# Drive.net
KiCad netlist of a schematic drawn in Altium Designer
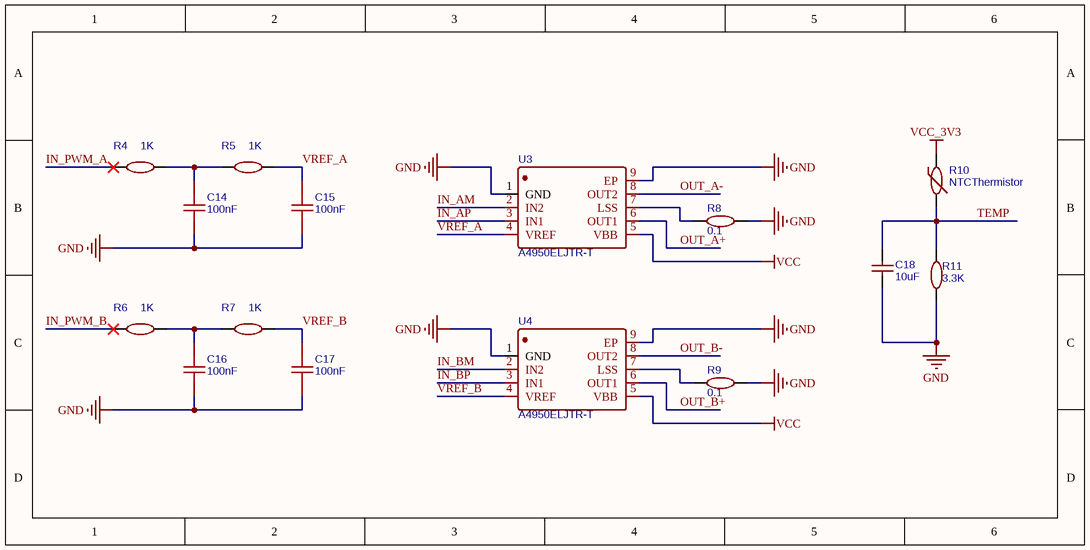
[diagram p0: Drive.SchDoc]

(export (version "E")
  (design (tool "Eeschema 10.0.6"))
  (components
    (comp (ref "C14")
      (value "100nF")
      (footprint "C0603")
      (fields
        (field (name "BOM_MANUFACTURER PART") "CL10B104KB8NNNC")
        (field (name "BOM_SUPPLIER PART") "C1591")
      )
      (libsource (lib "0.1uF") (part "100nF"))
    )
    (comp (ref "C15")
      (value "100nF")
      (footprint "C0603")
      (fields
        (field (name "BOM_MANUFACTURER PART") "CL10B104KB8NNNC")
        (field (name "BOM_SUPPLIER PART") "C1591")
      )
      (libsource (lib "0.1uF") (part "100nF"))
    )
    (comp (ref "C16")
      (value "100nF")
      (footprint "C0603")
      (fields
        (field (name "BOM_MANUFACTURER PART") "CL10B104KB8NNNC")
        (field (name "BOM_SUPPLIER PART") "C1591")
      )
      (libsource (lib "0.1uF") (part "100nF"))
    )
    (comp (ref "C17")
      (value "100nF")
      (footprint "C0603")
      (fields
        (field (name "BOM_MANUFACTURER PART") "CL10B104KB8NNNC")
        (field (name "BOM_SUPPLIER PART") "C1591")
      )
      (libsource (lib "0.1uF") (part "100nF"))
    )
    (comp (ref "C18")
      (value "10uF")
      (footprint "C1206")
      (fields
        (field (name "BOM_MANUFACTURER PART") "CL31A106KBHNNNE")
        (field (name "BOM_SUPPLIER PART") "C13585")
      )
      (libsource (lib "10uF") (part "10uF"))
    )
    (comp (ref "R4")
      (value "1K")
      (footprint "R0603")
      (fields
        (field (name "BOM_MANUFACTURER PART") "0603WAF1001T5E")
        (field (name "BOM_SUPPLIER PART") "C21190")
      )
      (libsource (lib "1K") (part "1K"))
    )
    (comp (ref "R5")
      (value "1K")
      (footprint "R0603")
      (fields
        (field (name "BOM_MANUFACTURER PART") "0603WAF1001T5E")
        (field (name "BOM_SUPPLIER PART") "C21190")
      )
      (libsource (lib "1K") (part "1K"))
    )
    (comp (ref "R6")
      (value "1K")
      (footprint "R0603")
      (fields
        (field (name "BOM_MANUFACTURER PART") "0603WAF1001T5E")
        (field (name "BOM_SUPPLIER PART") "C21190")
      )
      (libsource (lib "1K") (part "1K"))
    )
    (comp (ref "R7")
      (value "1K")
      (footprint "R0603")
      (fields
        (field (name "BOM_MANUFACTURER PART") "0603WAF1001T5E")
        (field (name "BOM_SUPPLIER PART") "C21190")
      )
      (libsource (lib "1K") (part "1K"))
    )
    (comp (ref "R8")
      (value "0.1")
      (footprint "R1206")
      (fields
        (field (name "BOM_MANUFACTURER PART") "1206W4F100LT5E")
        (field (name "BOM_SUPPLIER PART") "C25334")
      )
      (libsource (lib "0.1R") (part "0.1"))
    )
    (comp (ref "R9")
      (value "0.1")
      (footprint "R1206")
      (fields
        (field (name "BOM_MANUFACTURER PART") "1206W4F100LT5E")
        (field (name "BOM_SUPPLIER PART") "C25334")
      )
      (libsource (lib "0.1R") (part "0.1"))
    )
    (comp (ref "R10")
      (value "NTCThermistor")
      (footprint "R0402")
      (fields
        (field (name "BOM_MANUFACTURER PART") "NCP15XH103F03RC")
        (field (name "BOM_SUPPLIER PART") "C77131")
      )
      (libsource (lib "10K THERMISTOR") (part "NTCThermistor"))
    )
    (comp (ref "R11")
      (value "3.3K")
      (footprint "R0603_NEW")
      (fields
        (field (name "BOM_MANUFACTURER PART") "0603WAF3301T5E")
        (field (name "BOM_SUPPLIER PART") "C22978")
      )
      (libsource (lib "3.3K") (part "3.3K"))
    )
    (comp (ref "U3")
      (value "A4950ELJTR-T")
      (footprint "SOIC-8_L4.9-W3.9-P1.27-LS6.0-BL-EP")
      (fields (field (name "BOM_SUPPLIER PART") "C82404"))
      (libsource (lib "A4950") (part "A4950ELJTR-T"))
    )
    (comp (ref "U4")
      (value "A4950ELJTR-T")
      (footprint "SOIC-8_L4.9-W3.9-P1.27-LS6.0-BL-EP")
      (fields (field (name "BOM_SUPPLIER PART") "C82404"))
      (libsource (lib "A4950") (part "A4950ELJTR-T"))
    )
  )
  (nets
    (net (code "1") (name "/IN_AM") (class "Default")
      (node (ref "U3") (pin "2") (pinfunction "IN2_2") (pintype "passive"))
    )
    (net (code "2") (name "/IN_AP") (class "Default")
      (node (ref "U3") (pin "3") (pinfunction "IN1_3") (pintype "passive"))
    )
    (net (code "3") (name "/IN_BM") (class "Default")
      (node (ref "U4") (pin "2") (pinfunction "IN2_2") (pintype "passive"))
    )
    (net (code "4") (name "/IN_BP") (class "Default")
      (node (ref "U4") (pin "3") (pinfunction "IN1_3") (pintype "passive"))
    )
    (net (code "5") (name "/IN_PWM_A") (class "Default")
      (node (ref "R4") (pin "1") (pinfunction "1_1") (pintype "passive+no_connect"))
    )
    (net (code "6") (name "/IN_PWM_B") (class "Default")
      (node (ref "R6") (pin "1") (pinfunction "1_1") (pintype "passive+no_connect"))
    )
    (net (code "7") (name "/OUT_A+") (class "Default")
      (node (ref "U3") (pin "6") (pinfunction "OUT1_6") (pintype "passive"))
    )
    (net (code "8") (name "/OUT_A-") (class "Default")
      (node (ref "U3") (pin "8") (pinfunction "OUT2_8") (pintype "passive"))
    )
    (net (code "9") (name "/OUT_B+") (class "Default")
      (node (ref "U4") (pin "6") (pinfunction "OUT1_6") (pintype "passive"))
    )
    (net (code "10") (name "/OUT_B-") (class "Default")
      (node (ref "U4") (pin "8") (pinfunction "OUT2_8") (pintype "passive"))
    )
    (net (code "11") (name "/TEMP") (class "Default")
      (node (ref "C18") (pin "2") (pinfunction "2_2") (pintype "passive"))
      (node (ref "R10") (pin "2") (pinfunction "2_2") (pintype "passive"))
      (node (ref "R11") (pin "2") (pinfunction "2_2") (pintype "passive"))
    )
    (net (code "12") (name "/VREF_A") (class "Default")
      (node (ref "C15") (pin "2") (pinfunction "2_2") (pintype "passive"))
      (node (ref "R5") (pin "2") (pinfunction "2_2") (pintype "passive"))
      (node (ref "U3") (pin "4") (pinfunction "VREF_4") (pintype "passive"))
    )
    (net (code "13") (name "/VREF_B") (class "Default")
      (node (ref "C17") (pin "2") (pinfunction "2_2") (pintype "passive"))
      (node (ref "R7") (pin "2") (pinfunction "2_2") (pintype "passive"))
      (node (ref "U4") (pin "4") (pinfunction "VREF_4") (pintype "passive"))
    )
    (net (code "14") (name "GND") (class "Default")
      (node (ref "C14") (pin "1") (pinfunction "1_1") (pintype "passive"))
      (node (ref "C15") (pin "1") (pinfunction "1_1") (pintype "passive"))
      (node (ref "C16") (pin "1") (pinfunction "1_1") (pintype "passive"))
      (node (ref "C17") (pin "1") (pinfunction "1_1") (pintype "passive"))
      (node (ref "C18") (pin "1") (pinfunction "1_1") (pintype "passive"))
      (node (ref "R11") (pin "1") (pinfunction "1_1") (pintype "passive"))
      (node (ref "R8") (pin "2") (pinfunction "2_2") (pintype "passive"))
      (node (ref "R9") (pin "2") (pinfunction "2_2") (pintype "passive"))
      (node (ref "U3") (pin "1") (pinfunction "GND_1") (pintype "passive"))
      (node (ref "U3") (pin "9") (pinfunction "EP_9") (pintype "passive"))
      (node (ref "U4") (pin "1") (pinfunction "GND_1") (pintype "passive"))
      (node (ref "U4") (pin "9") (pinfunction "EP_9") (pintype "passive"))
    )
    (net (code "15") (name "Net-(C14-Pad2)") (class "Default")
      (node (ref "C14") (pin "2") (pinfunction "2_2") (pintype "passive"))
      (node (ref "R4") (pin "2") (pinfunction "2_2") (pintype "passive"))
      (node (ref "R5") (pin "1") (pinfunction "1_1") (pintype "passive"))
    )
    (net (code "16") (name "Net-(C16-Pad2)") (class "Default")
      (node (ref "C16") (pin "2") (pinfunction "2_2") (pintype "passive"))
      (node (ref "R6") (pin "2") (pinfunction "2_2") (pintype "passive"))
      (node (ref "R7") (pin "1") (pinfunction "1_1") (pintype "passive"))
    )
    (net (code "17") (name "Net-(U3-LSS)") (class "Default")
      (node (ref "R8") (pin "1") (pinfunction "1_1") (pintype "passive"))
      (node (ref "U3") (pin "7") (pinfunction "LSS_7") (pintype "passive"))
    )
    (net (code "18") (name "Net-(U4-LSS)") (class "Default")
      (node (ref "R9") (pin "1") (pinfunction "1_1") (pintype "passive"))
      (node (ref "U4") (pin "7") (pinfunction "LSS_7") (pintype "passive"))
    )
    (net (code "19") (name "VCC") (class "Default")
      (node (ref "U3") (pin "5") (pinfunction "VBB_5") (pintype "passive"))
      (node (ref "U4") (pin "5") (pinfunction "VBB_5") (pintype "passive"))
    )
    (net (code "20") (name "VCC_3V3") (class "Default")
      (node (ref "R10") (pin "1") (pinfunction "1_1") (pintype "passive"))
    )
  )
)
